# Supplies_LDOs.net
KiCad netlist of a schematic drawn in Altium Designer
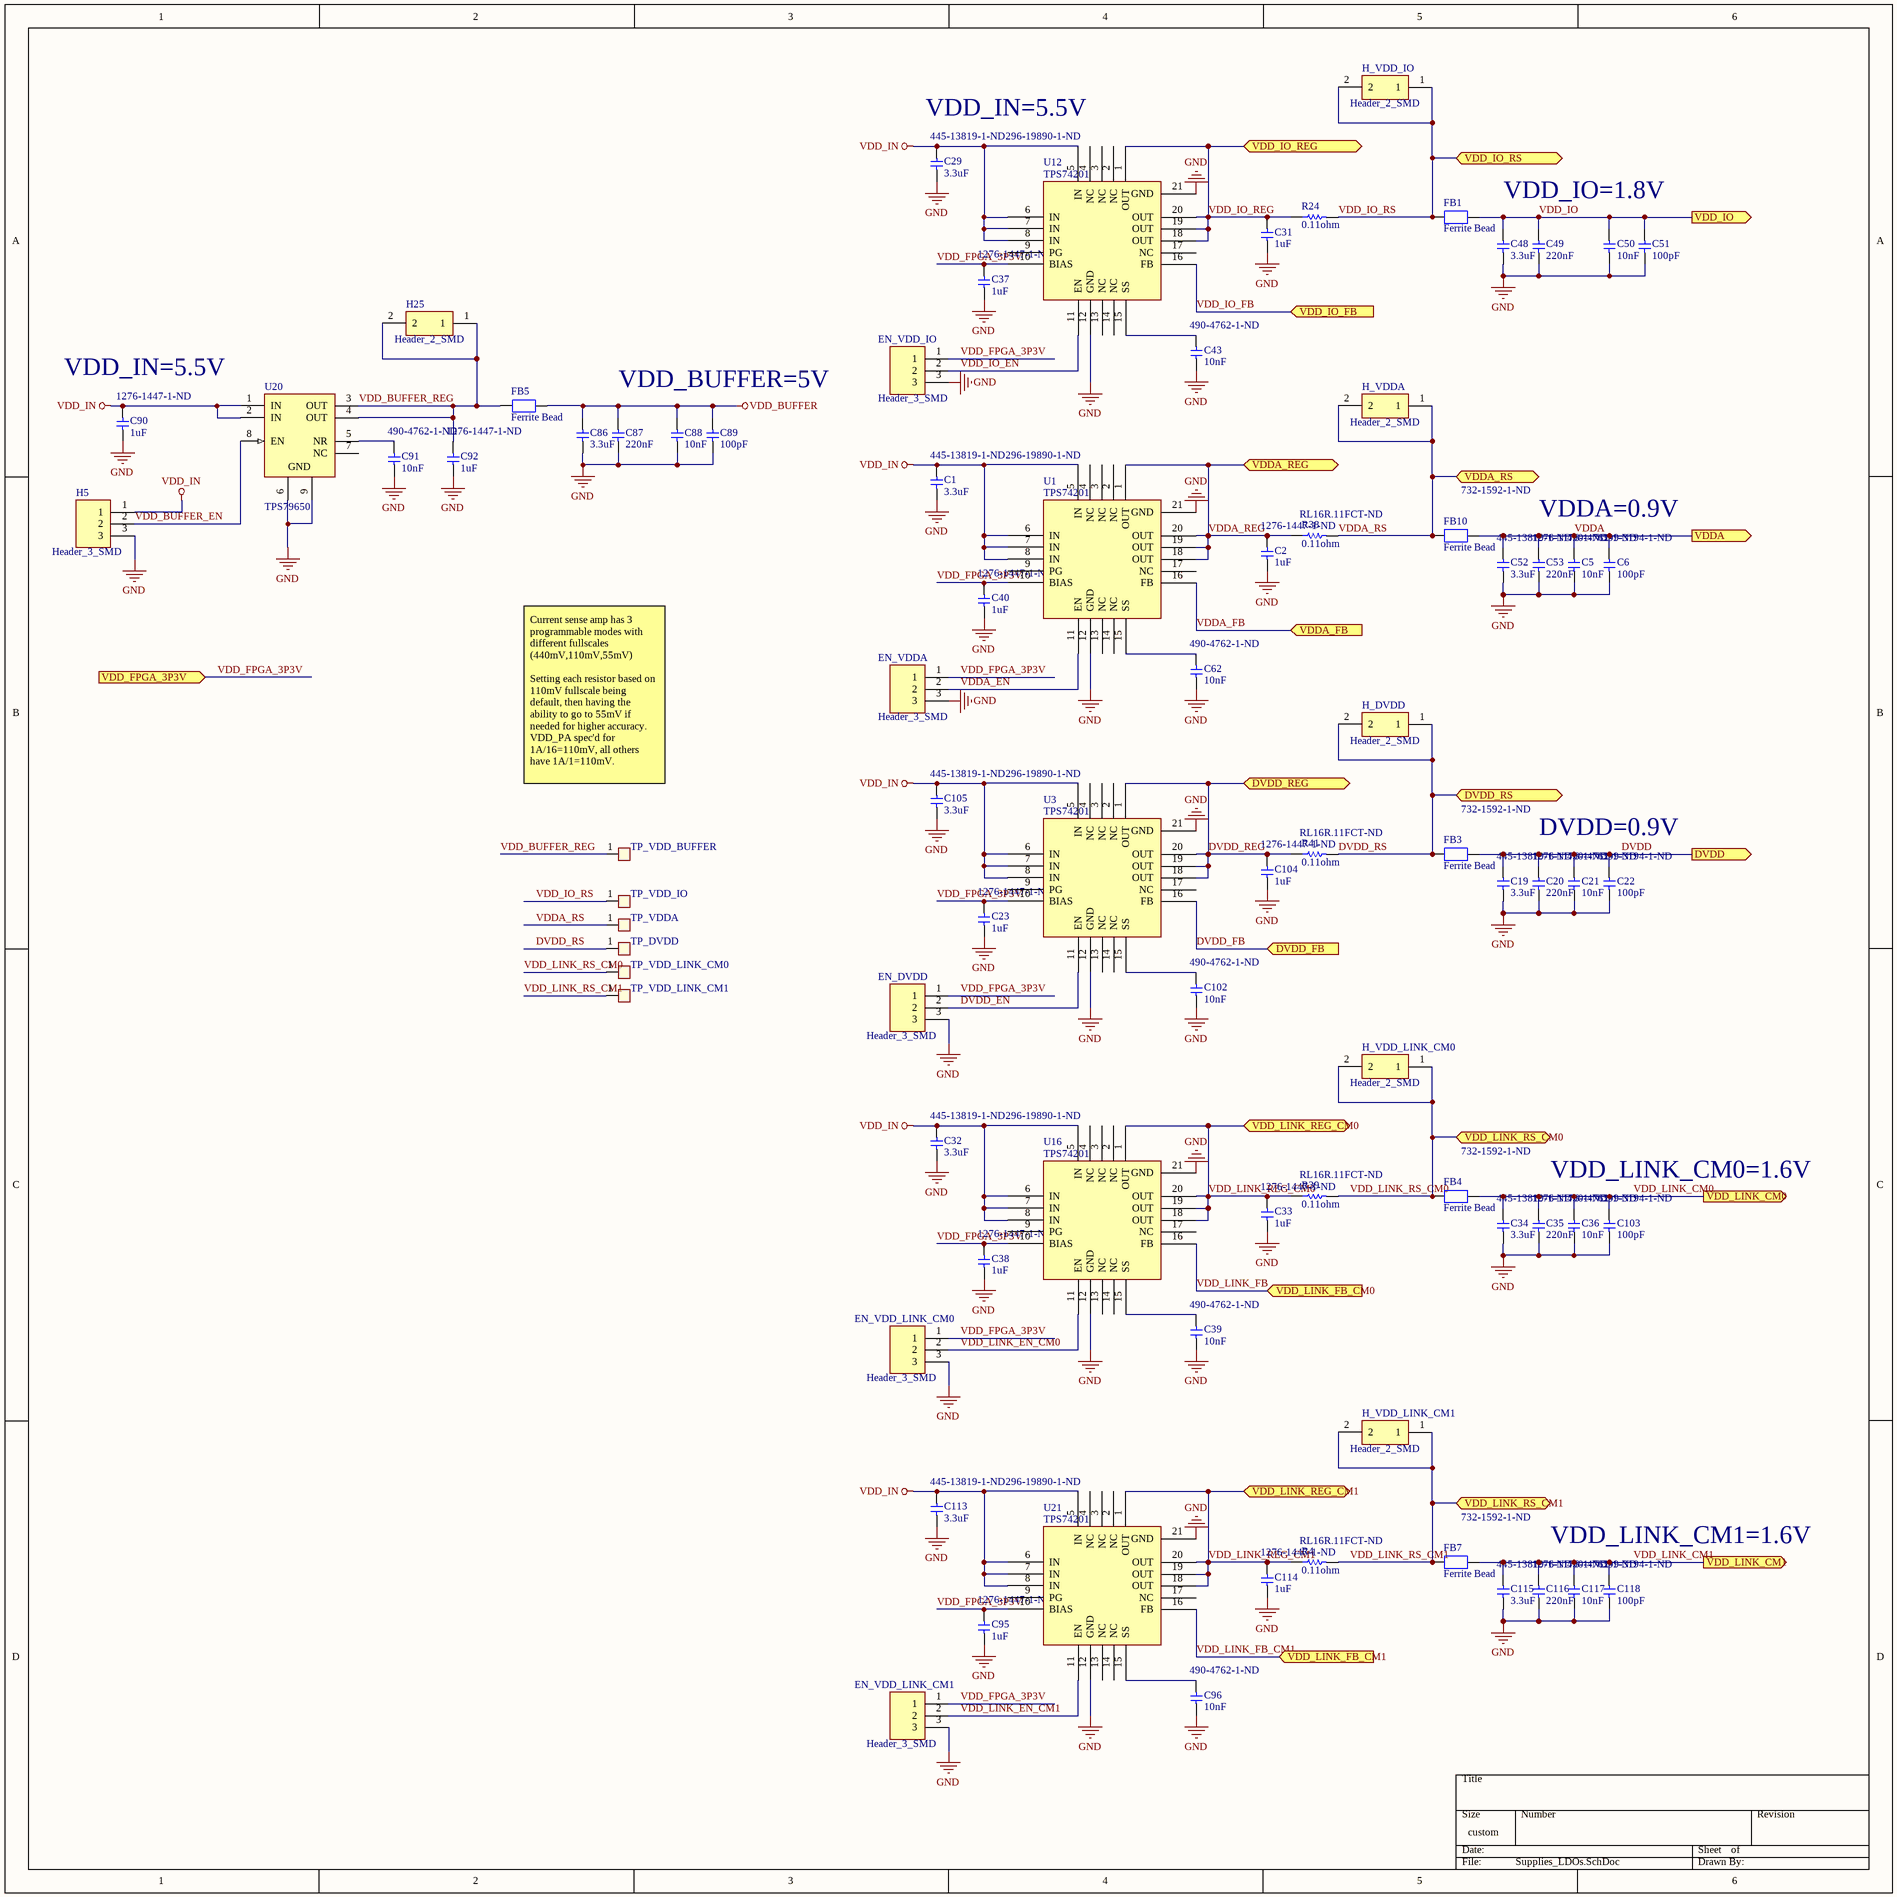
[diagram p0: Supplies_LDOs.SchDoc]

(export (version "E")
  (design (tool "Eeschema 10.0.6"))
  (components
    (comp (ref "C1")
      (value "3.3uF")
      (footprint "CAP_0402")
      (description "CAP CER 3.3uF 10% 10V X5R 0402")
      (fields (field (name "MANUFACTURER") "TDK") (field (name "SUPPLIER PART NUMBER 1") "445-13819-1-ND"))
      (libsource (lib "fader2_parts") (part "cap 3p3uF"))
    )
    (comp (ref "C2")
      (value "1uF")
      (footprint "CAP_0402")
      (description "CAP CER 1uF 20% 16V X5R 0402")
      (fields
        (field (name "MANUFACTURER") "Samsung Electro-Mechanics")
        (field (name "SUPPLIER PART NUMBER 1") "1276-1447-1-ND")
      )
      (libsource (lib "fader2_parts") (part "cap 1uF 0402"))
    )
    (comp (ref "C5")
      (value "10nF")
      (footprint "CAPC1005X06L_HD")
      (description "CAP CER 10nF 10% 50V X7R 0402")
      (fields (field (name "MANUFACTURER") "Murata") (field (name "SUPPLIER PART NUMBER 1") "490-4762-1-ND"))
      (libsource (lib "fader2_parts") (part "cap 10nF"))
    )
    (comp (ref "C6")
      (value "100pF")
      (footprint "CAPC1005X06L_HD")
      (description "CAP CER 100pF 5% 50V C0G/NP0 0402")
      (fields (field (name "MANUFACTURER") "Kemet") (field (name "SUPPLIER PART NUMBER 1") "399-3194-1-ND"))
      (libsource (lib "fader2_parts") (part "cap 100pF 0402"))
    )
    (comp (ref "C19")
      (value "3.3uF")
      (footprint "CAP_0402")
      (description "CAP CER 3.3uF 10% 10V X5R 0402")
      (fields (field (name "MANUFACTURER") "TDK") (field (name "SUPPLIER PART NUMBER 1") "445-13819-1-ND"))
      (libsource (lib "fader2_parts") (part "cap 3p3uF"))
    )
    (comp (ref "C20")
      (value "220nF")
      (footprint "CAP_0402")
      (description "CAP CER 0.22uF 10% 16V X7R 0402")
      (fields
        (field (name "MANUFACTURER") "Samsung Electro-Mechanics")
        (field (name "SUPPLIER PART NUMBER 1") "1276-1176-1-ND")
      )
      (libsource (lib "fader2_parts") (part "cap 220nF"))
    )
    (comp (ref "C21")
      (value "10nF")
      (footprint "CAPC1005X06L_HD")
      (description "CAP CER 10nF 10% 50V X7R 0402")
      (fields (field (name "MANUFACTURER") "Murata") (field (name "SUPPLIER PART NUMBER 1") "490-4762-1-ND"))
      (libsource (lib "fader2_parts") (part "cap 10nF"))
    )
    (comp (ref "C22")
      (value "100pF")
      (footprint "CAPC1005X06L_HD")
      (description "CAP CER 100pF 5% 50V C0G/NP0 0402")
      (fields (field (name "MANUFACTURER") "Kemet") (field (name "SUPPLIER PART NUMBER 1") "399-3194-1-ND"))
      (libsource (lib "fader2_parts") (part "cap 100pF 0402"))
    )
    (comp (ref "C23")
      (value "1uF")
      (footprint "CAP_0402")
      (description "CAP CER 1uF 20% 16V X5R 0402")
      (fields
        (field (name "MANUFACTURER") "Samsung Electro-Mechanics")
        (field (name "SUPPLIER PART NUMBER 1") "1276-1447-1-ND")
      )
      (libsource (lib "fader2_parts") (part "cap 1uF 0402"))
    )
    (comp (ref "C29")
      (value "3.3uF")
      (footprint "CAP_0402")
      (description "CAP CER 3.3uF 10% 10V X5R 0402")
      (fields (field (name "MANUFACTURER") "TDK") (field (name "SUPPLIER PART NUMBER 1") "445-13819-1-ND"))
      (libsource (lib "fader2_parts") (part "cap 3p3uF"))
    )
    (comp (ref "C31")
      (value "1uF")
      (footprint "CAP_0402")
      (description "CAP CER 1uF 20% 16V X5R 0402")
      (fields (field (name "MANUFACTURER") "Samsung Electro-Mechanics"))
      (libsource (lib "fader2_parts") (part "cap 1uF 0402"))
    )
    (comp (ref "C32")
      (value "3.3uF")
      (footprint "CAP_0402")
      (description "CAP CER 3.3uF 10% 10V X5R 0402")
      (fields (field (name "MANUFACTURER") "TDK") (field (name "SUPPLIER PART NUMBER 1") "445-13819-1-ND"))
      (libsource (lib "fader2_parts") (part "cap 3p3uF"))
    )
    (comp (ref "C33")
      (value "1uF")
      (footprint "CAP_0402")
      (description "CAP CER 1uF 20% 16V X5R 0402")
      (fields
        (field (name "MANUFACTURER") "Samsung Electro-Mechanics")
        (field (name "SUPPLIER PART NUMBER 1") "1276-1447-1-ND")
      )
      (libsource (lib "fader2_parts") (part "cap 1uF 0402"))
    )
    (comp (ref "C34")
      (value "3.3uF")
      (footprint "CAP_0402")
      (description "CAP CER 3.3uF 10% 10V X5R 0402")
      (fields (field (name "MANUFACTURER") "TDK") (field (name "SUPPLIER PART NUMBER 1") "445-13819-1-ND"))
      (libsource (lib "fader2_parts") (part "cap 3p3uF"))
    )
    (comp (ref "C35")
      (value "220nF")
      (footprint "CAP_0402")
      (description "CAP CER 0.22uF 10% 16V X7R 0402")
      (fields
        (field (name "MANUFACTURER") "Samsung Electro-Mechanics")
        (field (name "SUPPLIER PART NUMBER 1") "1276-1176-1-ND")
      )
      (libsource (lib "fader2_parts") (part "cap 220nF"))
    )
    (comp (ref "C36")
      (value "10nF")
      (footprint "CAPC1005X06L_HD")
      (description "CAP CER 10nF 10% 50V X7R 0402")
      (fields (field (name "MANUFACTURER") "Murata") (field (name "SUPPLIER PART NUMBER 1") "490-4762-1-ND"))
      (libsource (lib "fader2_parts") (part "cap 10nF"))
    )
    (comp (ref "C37")
      (value "1uF")
      (footprint "CAP_0402")
      (description "CAP CER 1uF 20% 16V X5R 0402")
      (fields
        (field (name "MANUFACTURER") "Samsung Electro-Mechanics")
        (field (name "SUPPLIER PART NUMBER 1") "1276-1447-1-ND")
      )
      (libsource (lib "fader2_parts") (part "cap 1uF 0402"))
    )
    (comp (ref "C38")
      (value "1uF")
      (footprint "CAP_0402")
      (description "CAP CER 1uF 20% 16V X5R 0402")
      (fields
        (field (name "MANUFACTURER") "Samsung Electro-Mechanics")
        (field (name "SUPPLIER PART NUMBER 1") "1276-1447-1-ND")
      )
      (libsource (lib "fader2_parts") (part "cap 1uF 0402"))
    )
    (comp (ref "C39")
      (value "10nF")
      (footprint "CAPC1005X06L_HD")
      (description "CAP CER 10nF 10% 50V X7R 0402")
      (fields (field (name "MANUFACTURER") "Murata") (field (name "SUPPLIER PART NUMBER 1") "490-4762-1-ND"))
      (libsource (lib "fader2_parts") (part "cap 10nF"))
    )
    (comp (ref "C40")
      (value "1uF")
      (footprint "CAP_0402")
      (description "CAP CER 1uF 20% 16V X5R 0402")
      (fields
        (field (name "MANUFACTURER") "Samsung Electro-Mechanics")
        (field (name "SUPPLIER PART NUMBER 1") "1276-1447-1-ND")
      )
      (libsource (lib "fader2_parts") (part "cap 1uF 0402"))
    )
    (comp (ref "C43")
      (value "10nF")
      (footprint "CAPC1005X06L_HD")
      (description "CAP CER 10nF 10% 50V X7R 0402")
      (fields (field (name "MANUFACTURER") "Murata") (field (name "SUPPLIER PART NUMBER 1") "490-4762-1-ND"))
      (libsource (lib "fader2_parts") (part "cap 10nF"))
    )
    (comp (ref "C48")
      (value "3.3uF")
      (footprint "CAP_0402")
      (description "CAP CER 3.3uF 10% 10V X5R 0402")
      (fields (field (name "MANUFACTURER") "TDK"))
      (libsource (lib "fader2_parts") (part "cap 3p3uF"))
    )
    (comp (ref "C49")
      (value "220nF")
      (footprint "CAP_0402")
      (description "CAP CER 0.22uF 10% 16V X7R 0402")
      (fields (field (name "MANUFACTURER") "Samsung Electro-Mechanics"))
      (libsource (lib "fader2_parts") (part "cap 220nF"))
    )
    (comp (ref "C50")
      (value "10nF")
      (footprint "CAPC1005X06L_HD")
      (description "CAP CER 10nF 10% 50V X7R 0402")
      (fields (field (name "MANUFACTURER") "Murata"))
      (libsource (lib "fader2_parts") (part "cap 10nF"))
    )
    (comp (ref "C51")
      (value "100pF")
      (footprint "CAPC1005X06L_HD")
      (description "CAP CER 100pF 5% 50V C0G/NP0 0402")
      (fields (field (name "MANUFACTURER") "Kemet"))
      (libsource (lib "fader2_parts") (part "cap 100pF 0402"))
    )
    (comp (ref "C52")
      (value "3.3uF")
      (footprint "CAP_0402")
      (description "CAP CER 3.3uF 10% 10V X5R 0402")
      (fields (field (name "MANUFACTURER") "TDK") (field (name "SUPPLIER PART NUMBER 1") "445-13819-1-ND"))
      (libsource (lib "fader2_parts") (part "cap 3p3uF"))
    )
    (comp (ref "C53")
      (value "220nF")
      (footprint "CAP_0402")
      (description "CAP CER 0.22uF 10% 16V X7R 0402")
      (fields
        (field (name "MANUFACTURER") "Samsung Electro-Mechanics")
        (field (name "SUPPLIER PART NUMBER 1") "1276-1176-1-ND")
      )
      (libsource (lib "fader2_parts") (part "cap 220nF"))
    )
    (comp (ref "C62")
      (value "10nF")
      (footprint "CAPC1005X06L_HD")
      (description "CAP CER 10nF 10% 50V X7R 0402")
      (fields (field (name "MANUFACTURER") "Murata") (field (name "SUPPLIER PART NUMBER 1") "490-4762-1-ND"))
      (libsource (lib "fader2_parts") (part "cap 10nF"))
    )
    (comp (ref "C86")
      (value "3.3uF")
      (footprint "CAP_0402")
      (description "CAP CER 3.3uF 10% 10V X5R 0402")
      (fields (field (name "MANUFACTURER") "TDK"))
      (libsource (lib "fader2_parts") (part "cap 3p3uF"))
    )
    (comp (ref "C87")
      (value "220nF")
      (footprint "CAP_0402")
      (description "CAP CER 0.22uF 10% 16V X7R 0402")
      (fields (field (name "MANUFACTURER") "Samsung Electro-Mechanics"))
      (libsource (lib "fader2_parts") (part "cap 220nF"))
    )
    (comp (ref "C88")
      (value "10nF")
      (footprint "CAPC1005X06L_HD")
      (description "CAP CER 10nF 10% 50V X7R 0402")
      (fields (field (name "MANUFACTURER") "Murata"))
      (libsource (lib "fader2_parts") (part "cap 10nF"))
    )
    (comp (ref "C89")
      (value "100pF")
      (footprint "CAPC1005X06L_HD")
      (description "CAP CER 100pF 5% 50V C0G/NP0 0402")
      (fields (field (name "MANUFACTURER") "Kemet"))
      (libsource (lib "fader2_parts") (part "cap 100pF 0402"))
    )
    (comp (ref "C90")
      (value "1uF")
      (footprint "CAP_0402")
      (description "CAP CER 1uF 20% 16V X5R 0402")
      (fields
        (field (name "MANUFACTURER") "Samsung Electro-Mechanics")
        (field (name "SUPPLIER PART NUMBER 1") "1276-1447-1-ND")
      )
      (libsource (lib "fader2_parts") (part "cap 1uF 0402"))
    )
    (comp (ref "C91")
      (value "10nF")
      (footprint "CAPC1005X06L_HD")
      (description "CAP CER 10nF 10% 50V X7R 0402")
      (fields (field (name "MANUFACTURER") "Murata") (field (name "SUPPLIER PART NUMBER 1") "490-4762-1-ND"))
      (libsource (lib "fader2_parts") (part "cap 10nF"))
    )
    (comp (ref "C92")
      (value "1uF")
      (footprint "CAP_0402")
      (description "CAP CER 1uF 20% 16V X5R 0402")
      (fields
        (field (name "MANUFACTURER") "Samsung Electro-Mechanics")
        (field (name "SUPPLIER PART NUMBER 1") "1276-1447-1-ND")
      )
      (libsource (lib "fader2_parts") (part "cap 1uF 0402"))
    )
    (comp (ref "C95")
      (value "1uF")
      (footprint "CAP_0402")
      (description "CAP CER 1uF 20% 16V X5R 0402")
      (fields
        (field (name "MANUFACTURER") "Samsung Electro-Mechanics")
        (field (name "SUPPLIER PART NUMBER 1") "1276-1447-1-ND")
      )
      (libsource (lib "fader2_parts") (part "cap 1uF 0402"))
    )
    (comp (ref "C96")
      (value "10nF")
      (footprint "CAPC1005X06L_HD")
      (description "CAP CER 10nF 10% 50V X7R 0402")
      (fields (field (name "MANUFACTURER") "Murata") (field (name "SUPPLIER PART NUMBER 1") "490-4762-1-ND"))
      (libsource (lib "fader2_parts") (part "cap 10nF"))
    )
    (comp (ref "C102")
      (value "10nF")
      (footprint "CAPC1005X06L_HD")
      (description "CAP CER 10nF 10% 50V X7R 0402")
      (fields (field (name "MANUFACTURER") "Murata") (field (name "SUPPLIER PART NUMBER 1") "490-4762-1-ND"))
      (libsource (lib "fader2_parts") (part "cap 10nF"))
    )
    (comp (ref "C103")
      (value "100pF")
      (footprint "CAPC1005X06L_HD")
      (description "CAP CER 100pF 5% 50V C0G/NP0 0402")
      (fields (field (name "MANUFACTURER") "Kemet") (field (name "SUPPLIER PART NUMBER 1") "399-3194-1-ND"))
      (libsource (lib "fader2_parts") (part "cap 100pF 0402"))
    )
    (comp (ref "C104")
      (value "1uF")
      (footprint "CAP_0402")
      (description "CAP CER 1uF 20% 16V X5R 0402")
      (fields
        (field (name "MANUFACTURER") "Samsung Electro-Mechanics")
        (field (name "SUPPLIER PART NUMBER 1") "1276-1447-1-ND")
      )
      (libsource (lib "fader2_parts") (part "cap 1uF 0402"))
    )
    (comp (ref "C105")
      (value "3.3uF")
      (footprint "CAP_0402")
      (description "CAP CER 3.3uF 10% 10V X5R 0402")
      (fields (field (name "MANUFACTURER") "TDK") (field (name "SUPPLIER PART NUMBER 1") "445-13819-1-ND"))
      (libsource (lib "fader2_parts") (part "cap 3p3uF"))
    )
    (comp (ref "C113")
      (value "3.3uF")
      (footprint "CAP_0402")
      (description "CAP CER 3.3uF 10% 10V X5R 0402")
      (fields (field (name "MANUFACTURER") "TDK") (field (name "SUPPLIER PART NUMBER 1") "445-13819-1-ND"))
      (libsource (lib "fader2_parts") (part "cap 3p3uF"))
    )
    (comp (ref "C114")
      (value "1uF")
      (footprint "CAP_0402")
      (description "CAP CER 1uF 20% 16V X5R 0402")
      (fields
        (field (name "MANUFACTURER") "Samsung Electro-Mechanics")
        (field (name "SUPPLIER PART NUMBER 1") "1276-1447-1-ND")
      )
      (libsource (lib "fader2_parts") (part "cap 1uF 0402"))
    )
    (comp (ref "C115")
      (value "3.3uF")
      (footprint "CAP_0402")
      (description "CAP CER 3.3uF 10% 10V X5R 0402")
      (fields (field (name "MANUFACTURER") "TDK") (field (name "SUPPLIER PART NUMBER 1") "445-13819-1-ND"))
      (libsource (lib "fader2_parts") (part "cap 3p3uF"))
    )
    (comp (ref "C116")
      (value "220nF")
      (footprint "CAP_0402")
      (description "CAP CER 0.22uF 10% 16V X7R 0402")
      (fields
        (field (name "MANUFACTURER") "Samsung Electro-Mechanics")
        (field (name "SUPPLIER PART NUMBER 1") "1276-1176-1-ND")
      )
      (libsource (lib "fader2_parts") (part "cap 220nF"))
    )
    (comp (ref "C117")
      (value "10nF")
      (footprint "CAPC1005X06L_HD")
      (description "CAP CER 10nF 10% 50V X7R 0402")
      (fields (field (name "MANUFACTURER") "Murata") (field (name "SUPPLIER PART NUMBER 1") "490-4762-1-ND"))
      (libsource (lib "fader2_parts") (part "cap 10nF"))
    )
    (comp (ref "C118")
      (value "100pF")
      (footprint "CAPC1005X06L_HD")
      (description "CAP CER 100pF 5% 50V C0G/NP0 0402")
      (fields (field (name "MANUFACTURER") "Kemet") (field (name "SUPPLIER PART NUMBER 1") "399-3194-1-ND"))
      (libsource (lib "fader2_parts") (part "cap 100pF 0402"))
    )
    (comp (ref "EN_DVDD")
      (value "Header_3_SMD")
      (footprint "HDR1X3_SMD")
      (description "Connector Header Vertical, SMD, 3 position 0.100\" (2.54mm)")
      (fields
        (field (name "MANUFACTURER_PART_NUMBER") "TSM-103-01-S-SV-P-TR")
        (field (name "MOUSER PART NUMBER") "200-TSM10301SSVPTR")
      )
      (libsource (lib "fader2_parts") (part "Header_3_SMD"))
    )
    (comp (ref "EN_VDDA")
      (value "Header_3_SMD")
      (footprint "HDR1X3_SMD")
      (description "Connector Header Vertical, SMD, 3 position 0.100\" (2.54mm)")
      (fields
        (field (name "MANUFACTURER_PART_NUMBER") "TSM-103-01-S-SV-P-TR")
        (field (name "MOUSER PART NUMBER") "200-TSM10301SSVPTR")
      )
      (libsource (lib "fader2_parts") (part "Header_3_SMD"))
    )
    (comp (ref "EN_VDD_IO")
      (value "Header_3_SMD")
      (footprint "HDR1X3_SMD")
      (description "Connector Header Vertical, SMD, 3 position 0.100\" (2.54mm)")
      (fields
        (field (name "MANUFACTURER_PART_NUMBER") "TSM-103-01-S-SV-P-TR")
        (field (name "MOUSER PART NUMBER") "200-TSM10301SSVPTR")
      )
      (libsource (lib "fader2_parts") (part "Header_3_SMD"))
    )
    (comp (ref "EN_VDD_LINK_CM0")
      (value "Header_3_SMD")
      (footprint "HDR1X3_SMD")
      (description "Connector Header Vertical, SMD, 3 position 0.100\" (2.54mm)")
      (fields
        (field (name "MANUFACTURER_PART_NUMBER") "TSM-103-01-S-SV-P-TR")
        (field (name "MOUSER PART NUMBER") "200-TSM10301SSVPTR")
      )
      (libsource (lib "fader2_parts") (part "Header_3_SMD"))
    )
    (comp (ref "EN_VDD_LINK_CM1")
      (value "Header_3_SMD")
      (footprint "HDR1X3_SMD")
      (description "Connector Header Vertical, SMD, 3 position 0.100\" (2.54mm)")
      (fields
        (field (name "MANUFACTURER_PART_NUMBER") "TSM-103-01-S-SV-P-TR")
        (field (name "MOUSER PART NUMBER") "200-TSM10301SSVPTR")
      )
      (libsource (lib "fader2_parts") (part "Header_3_SMD"))
    )
    (comp (ref "FB1")
      (value "Ferrite Bead")
      (footprint "FER_SMD-0603")
      (description "Ferrite Bead 300 Ohms @ 100MHz 1 Signal Line 0603 (1608 Metric) 2A 150mOhm")
      (fields (field (name "MANUFACTURER") "Wurth"))
      (libsource (lib "fader2_parts") (part "Ferrite Bead"))
    )
    (comp (ref "FB3")
      (value "Ferrite Bead")
      (footprint "FER_SMD-0603")
      (description "Ferrite Bead 300 Ohms @ 100MHz 1 Signal Line 0603 (1608 Metric) 2A 150mOhm")
      (fields (field (name "MANUFACTURER") "Wurth") (field (name "SUPPLIER PART NUMBER 1") "732-1592-1-ND"))
      (libsource (lib "fader2_parts") (part "Ferrite Bead"))
    )
    (comp (ref "FB4")
      (value "Ferrite Bead")
      (footprint "FER_SMD-0603")
      (description "Ferrite Bead 300 Ohms @ 100MHz 1 Signal Line 0603 (1608 Metric) 2A 150mOhm")
      (fields (field (name "MANUFACTURER") "Wurth") (field (name "SUPPLIER PART NUMBER 1") "732-1592-1-ND"))
      (libsource (lib "fader2_parts") (part "Ferrite Bead"))
    )
    (comp (ref "FB5")
      (value "Ferrite Bead")
      (footprint "FER_SMD-0603")
      (description "Ferrite Bead 300 Ohms @ 100MHz 1 Signal Line 0603 (1608 Metric) 2A 150mOhm")
      (fields (field (name "MANUFACTURER") "Wurth"))
      (libsource (lib "fader2_parts") (part "Ferrite Bead"))
    )
    (comp (ref "FB7")
      (value "Ferrite Bead")
      (footprint "FER_SMD-0603")
      (description "Ferrite Bead 300 Ohms @ 100MHz 1 Signal Line 0603 (1608 Metric) 2A 150mOhm")
      (fields (field (name "MANUFACTURER") "Wurth") (field (name "SUPPLIER PART NUMBER 1") "732-1592-1-ND"))
      (libsource (lib "fader2_parts") (part "Ferrite Bead"))
    )
    (comp (ref "FB10")
      (value "Ferrite Bead")
      (footprint "FER_SMD-0603")
      (description "Ferrite Bead 300 Ohms @ 100MHz 1 Signal Line 0603 (1608 Metric) 2A 150mOhm")
      (fields (field (name "MANUFACTURER") "Wurth") (field (name "SUPPLIER PART NUMBER 1") "732-1592-1-ND"))
      (libsource (lib "fader2_parts") (part "Ferrite Bead"))
    )
    (comp (ref "H5")
      (value "Header_3_SMD")
      (footprint "HDR1X3_SMD")
      (description "Connector Header Vertical, SMD, 3 position 0.100\" (2.54mm)")
      (fields
        (field (name "MANUFACTURER_PART_NUMBER") "TSM-103-01-S-SV-P-TR")
        (field (name "MOUSER PART NUMBER") "200-TSM10301SSVPTR")
      )
      (libsource (lib "fader2_parts") (part "Header_3_SMD"))
    )
    (comp (ref "H25")
      (value "Header_2_SMD")
      (footprint "HDR1X2_SMD_S")
      (description "Connector Header Vertical, SMD, 2 position 0.100\" (2.54mm)")
      (fields
        (field (name "MANUFACTURER_PART_NUMBER") "TSM-102-01-S-SV")
        (field (name "MOUSER PART NUMBER") "200-TSM10201SSV")
      )
      (libsource (lib "fader2_parts") (part "Header_2_SMD"))
    )
    (comp (ref "H_DVDD")
      (value "Header_2_SMD")
      (footprint "HDR1X2_SMD_S")
      (description "Connector Header Vertical, SMD, 2 position 0.100\" (2.54mm)")
      (fields
        (field (name "MANUFACTURER_PART_NUMBER") "TSM-102-01-S-SV")
        (field (name "MOUSER PART NUMBER") "200-TSM10201SSV")
      )
      (libsource (lib "fader2_parts") (part "Header_2_SMD"))
    )
    (comp (ref "H_VDDA")
      (value "Header_2_SMD")
      (footprint "HDR1X2_SMD_S")
      (description "Connector Header Vertical, SMD, 2 position 0.100\" (2.54mm)")
      (fields
        (field (name "MANUFACTURER_PART_NUMBER") "TSM-102-01-S-SV")
        (field (name "MOUSER PART NUMBER") "200-TSM10201SSV")
      )
      (libsource (lib "fader2_parts") (part "Header_2_SMD"))
    )
    (comp (ref "H_VDD_IO")
      (value "Header_2_SMD")
      (footprint "HDR1X2_SMD_S")
      (description "Connector Header Vertical, SMD, 2 position 0.100\" (2.54mm)")
      (fields
        (field (name "MANUFACTURER_PART_NUMBER") "TSM-102-01-S-SV")
        (field (name "MOUSER PART NUMBER") "200-TSM10201SSV")
      )
      (libsource (lib "fader2_parts") (part "Header_2_SMD"))
    )
    (comp (ref "H_VDD_LINK_CM0")
      (value "Header_2_SMD")
      (footprint "HDR1X2_SMD_S")
      (description "Connector Header Vertical, SMD, 2 position 0.100\" (2.54mm)")
      (fields
        (field (name "MANUFACTURER_PART_NUMBER") "TSM-102-01-S-SV")
        (field (name "MOUSER PART NUMBER") "200-TSM10201SSV")
      )
      (libsource (lib "fader2_parts") (part "Header_2_SMD"))
    )
    (comp (ref "H_VDD_LINK_CM1")
      (value "Header_2_SMD")
      (footprint "HDR1X2_SMD_S")
      (description "Connector Header Vertical, SMD, 2 position 0.100\" (2.54mm)")
      (fields
        (field (name "MANUFACTURER_PART_NUMBER") "TSM-102-01-S-SV")
        (field (name "MOUSER PART NUMBER") "200-TSM10201SSV")
      )
      (libsource (lib "fader2_parts") (part "Header_2_SMD"))
    )
    (comp (ref "R4")
      (value "0.11ohm")
      (footprint "RES_1206")
      (description "RES 0.11 OHM 1% 1/2W 1206")
      (fields (field (name "MANUFACTURER") "Susumu") (field (name "SUPPLIER PART NUMBER 1") "RL16R.11FCT-ND"))
      (libsource (lib "fader2_parts") (part "res 0.11 ohm"))
    )
    (comp (ref "R24")
      (value "0.11ohm")
      (footprint "RES_1206")
      (description "RES 0.11 OHM 1% 1/2W 1206")
      (fields (field (name "MANUFACTURER") "Susumu"))
      (libsource (lib "fader2_parts") (part "res 0.11 ohm"))
    )
    (comp (ref "R38")
      (value "0.11ohm")
      (footprint "RES_1206")
      (description "RES 0.11 OHM 1% 1/2W 1206")
      (fields (field (name "MANUFACTURER") "Susumu") (field (name "SUPPLIER PART NUMBER 1") "RL16R.11FCT-ND"))
      (libsource (lib "fader2_parts") (part "res 0.11 ohm"))
    )
    (comp (ref "R39")
      (value "0.11ohm")
      (footprint "RES_1206")
      (description "RES 0.11 OHM 1% 1/2W 1206")
      (fields (field (name "MANUFACTURER") "Susumu") (field (name "SUPPLIER PART NUMBER 1") "RL16R.11FCT-ND"))
      (libsource (lib "fader2_parts") (part "res 0.11 ohm"))
    )
    (comp (ref "R41")
      (value "0.11ohm")
      (footprint "RES_1206")
      (description "RES 0.11 OHM 1% 1/2W 1206")
      (fields (field (name "MANUFACTURER") "Susumu") (field (name "SUPPLIER PART NUMBER 1") "RL16R.11FCT-ND"))
      (libsource (lib "fader2_parts") (part "res 0.11 ohm"))
    )
    (comp (ref "TP_DVDD")
      (value "TestPoint_SMD")
      (footprint "TestPoint_SMD")
      (description "Test Point, SMD 1mm x 1.8mm, 1.15mm high.")
      (libsource (lib "fader2_parts") (part "TestPoint_SMD"))
    )
    (comp (ref "TP_VDDA")
      (value "TestPoint_SMD")
      (footprint "TestPoint_SMD")
      (description "Test Point, SMD 1mm x 1.8mm, 1.15mm high.")
      (libsource (lib "fader2_parts") (part "TestPoint_SMD"))
    )
    (comp (ref "TP_VDD_BUFFER")
      (value "TestPoint_SMD")
      (footprint "TestPoint_SMD")
      (description "Test Point, SMD 1mm x 1.8mm, 1.15mm high.")
      (libsource (lib "fader2_parts") (part "TestPoint_SMD"))
    )
    (comp (ref "TP_VDD_IO")
      (value "TestPoint_SMD")
      (footprint "TestPoint_SMD")
      (description "Test Point, SMD 1mm x 1.8mm, 1.15mm high.")
      (libsource (lib "fader2_parts") (part "TestPoint_SMD"))
    )
    (comp (ref "TP_VDD_LINK_CM0")
      (value "TestPoint_SMD")
      (footprint "TestPoint_SMD")
      (description "Test Point, SMD 1mm x 1.8mm, 1.15mm high.")
      (libsource (lib "fader2_parts") (part "TestPoint_SMD"))
    )
    (comp (ref "TP_VDD_LINK_CM1")
      (value "TestPoint_SMD")
      (footprint "TestPoint_SMD")
      (description "Test Point, SMD 1mm x 1.8mm, 1.15mm high.")
      (libsource (lib "fader2_parts") (part "TestPoint_SMD"))
    )
    (comp (ref "U1")
      (value "TPS74201")
      (footprint "TPS74201_NPV")
      (description "Linear Positive Voltage Regulator IC, Adjustable Voltage, 1 Output 1.5A 20-VQFN (5x5)")
      (fields (field (name "MANUFACTURER") "TI") (field (name "SUPPLIER PART NUMBER 1") "296-19890-1-ND"))
      (libsource (lib "fader2_parts") (part "TPS74201"))
    )
    (comp (ref "U3")
      (value "TPS74201")
      (footprint "TPS74201_NPV")
      (description "Linear Positive Voltage Regulator IC, Adjustable Voltage, 1 Output 1.5A 20-VQFN (5x5)")
      (fields (field (name "MANUFACTURER") "TI") (field (name "SUPPLIER PART NUMBER 1") "296-19890-1-ND"))
      (libsource (lib "fader2_parts") (part "TPS74201"))
    )
    (comp (ref "U12")
      (value "TPS74201")
      (footprint "TPS74201_NPV")
      (description "Linear Positive Voltage Regulator IC, Adjustable Voltage, 1 Output 1.5A 20-VQFN (5x5)")
      (fields (field (name "MANUFACTURER") "TI") (field (name "SUPPLIER PART NUMBER 1") "296-19890-1-ND"))
      (libsource (lib "fader2_parts") (part "TPS74201"))
    )
    (comp (ref "U16")
      (value "TPS74201")
      (footprint "TPS74201_NPV")
      (description "Linear Positive Voltage Regulator IC, Adjustable Voltage, 1 Output 1.5A 20-VQFN (5x5)")
      (fields (field (name "MANUFACTURER") "TI") (field (name "SUPPLIER PART NUMBER 1") "296-19890-1-ND"))
      (libsource (lib "fader2_parts") (part "TPS74201"))
    )
    (comp (ref "U20")
      (value "TPS79650")
      (footprint "TI-DRB8-2400X1650TP_V")
      (fields (field (name "MANUFACTURER") "Texas Instruments") (field (name "PARTNUMBER") "TPS79650DRBR"))
      (libsource (lib "fader2_parts") (part "TPS79650DRBR"))
    )
    (comp (ref "U21")
      (value "TPS74201")
      (footprint "TPS74201_NPV")
      (description "Linear Positive Voltage Regulator IC, Adjustable Voltage, 1 Output 1.5A 20-VQFN (5x5)")
      (fields (field (name "MANUFACTURER") "TI") (field (name "SUPPLIER PART NUMBER 1") "296-19890-1-ND"))
      (libsource (lib "fader2_parts") (part "TPS74201"))
    )
  )
  (nets
    (net (code "1") (name "/DVDD") (class "Default")
      (node (ref "C19") (pin "1") (pinfunction "1_1") (pintype "passive"))
      (node (ref "C20") (pin "1") (pinfunction "1_1") (pintype "passive"))
      (node (ref "C21") (pin "1") (pinfunction "1_1") (pintype "passive"))
      (node (ref "C22") (pin "1") (pinfunction "1_1") (pintype "passive"))
      (node (ref "FB3") (pin "2") (pinfunction "2_2") (pintype "passive"))
    )
    (net (code "2") (name "/DVDD_EN") (class "Default")
      (node (ref "EN_DVDD") (pin "2") (pinfunction "2_2") (pintype "passive"))
      (node (ref "U3") (pin "11") (pinfunction "EN_11") (pintype "passive"))
    )
    (net (code "3") (name "/DVDD_FB") (class "Default")
      (node (ref "U3") (pin "16") (pinfunction "FB_16") (pintype "passive"))
    )
    (net (code "4") (name "/DVDD_REG") (class "Default")
      (node (ref "C104") (pin "1") (pinfunction "1_1") (pintype "passive"))
      (node (ref "R41") (pin "1") (pinfunction "TOP_1") (pintype "passive"))
      (node (ref "U3") (pin "1") (pinfunction "OUT_1") (pintype "passive"))
      (node (ref "U3") (pin "18") (pinfunction "OUT_18") (pintype "passive"))
      (node (ref "U3") (pin "19") (pinfunction "OUT_19") (pintype "passive"))
      (node (ref "U3") (pin "20") (pinfunction "OUT_20") (pintype "passive"))
    )
    (net (code "5") (name "/DVDD_RS") (class "Default")
      (node (ref "FB3") (pin "1") (pinfunction "1_1") (pintype "passive"))
      (node (ref "H_DVDD") (pin "1") (pinfunction "1_1") (pintype "passive"))
      (node (ref "H_DVDD") (pin "2") (pinfunction "2_2") (pintype "passive"))
      (node (ref "R41") (pin "2") (pinfunction "BOT_2") (pintype "passive"))
      (node (ref "TP_DVDD") (pin "1") (pinfunction "TP_1") (pintype "passive"))
    )
    (net (code "6") (name "/VDDA") (class "Default")
      (node (ref "C5") (pin "1") (pinfunction "1_1") (pintype "passive"))
      (node (ref "C52") (pin "1") (pinfunction "1_1") (pintype "passive"))
      (node (ref "C53") (pin "1") (pinfunction "1_1") (pintype "passive"))
      (node (ref "C6") (pin "1") (pinfunction "1_1") (pintype "passive"))
      (node (ref "FB10") (pin "2") (pinfunction "2_2") (pintype "passive"))
    )
    (net (code "7") (name "/VDDA_EN") (class "Default")
      (node (ref "EN_VDDA") (pin "2") (pinfunction "2_2") (pintype "passive"))
      (node (ref "U1") (pin "11") (pinfunction "EN_11") (pintype "passive"))
    )
    (net (code "8") (name "/VDDA_FB") (class "Default")
      (node (ref "U1") (pin "16") (pinfunction "FB_16") (pintype "passive"))
    )
    (net (code "9") (name "/VDDA_REG") (class "Default")
      (node (ref "C2") (pin "1") (pinfunction "1_1") (pintype "passive"))
      (node (ref "R38") (pin "1") (pinfunction "TOP_1") (pintype "passive"))
      (node (ref "U1") (pin "1") (pinfunction "OUT_1") (pintype "passive"))
      (node (ref "U1") (pin "18") (pinfunction "OUT_18") (pintype "passive"))
      (node (ref "U1") (pin "19") (pinfunction "OUT_19") (pintype "passive"))
      (node (ref "U1") (pin "20") (pinfunction "OUT_20") (pintype "passive"))
    )
    (net (code "10") (name "/VDDA_RS") (class "Default")
      (node (ref "FB10") (pin "1") (pinfunction "1_1") (pintype "passive"))
      (node (ref "H_VDDA") (pin "1") (pinfunction "1_1") (pintype "passive"))
      (node (ref "H_VDDA") (pin "2") (pinfunction "2_2") (pintype "passive"))
      (node (ref "R38") (pin "2") (pinfunction "BOT_2") (pintype "passive"))
      (node (ref "TP_VDDA") (pin "1") (pinfunction "TP_1") (pintype "passive"))
    )
    (net (code "11") (name "/VDD_BUFFER_EN") (class "Default")
      (node (ref "H5") (pin "2") (pinfunction "2_2") (pintype "passive"))
      (node (ref "U20") (pin "8") (pinfunction "EN_8") (pintype "input"))
    )
    (net (code "12") (name "/VDD_BUFFER_REG") (class "Default")
      (node (ref "C92") (pin "1") (pinfunction "1_1") (pintype "passive"))
      (node (ref "FB5") (pin "1") (pinfunction "1_1") (pintype "passive"))
      (node (ref "H25") (pin "1") (pinfunction "1_1") (pintype "passive"))
      (node (ref "H25") (pin "2") (pinfunction "2_2") (pintype "passive"))
      (node (ref "TP_VDD_BUFFER") (pin "1") (pinfunction "TP_1") (pintype "passive"))
      (node (ref "U20") (pin "3") (pinfunction "OUT_3") (pintype "power_in"))
      (node (ref "U20") (pin "4") (pinfunction "OUT_4") (pintype "power_in"))
    )
    (net (code "13") (name "/VDD_FPGA_3P3V") (class "Default")
      (node (ref "C23") (pin "1") (pinfunction "1_1") (pintype "passive"))
      (node (ref "C37") (pin "1") (pinfunction "1_1") (pintype "passive"))
      (node (ref "C38") (pin "1") (pinfunction "1_1") (pintype "passive"))
      (node (ref "C40") (pin "1") (pinfunction "1_1") (pintype "passive"))
      (node (ref "C95") (pin "1") (pinfunction "1_1") (pintype "passive"))
      (node (ref "EN_DVDD") (pin "1") (pinfunction "1_1") (pintype "passive"))
      (node (ref "EN_VDDA") (pin "1") (pinfunction "1_1") (pintype "passive"))
      (node (ref "EN_VDD_IO") (pin "1") (pinfunction "1_1") (pintype "passive"))
      (node (ref "EN_VDD_LINK_CM0") (pin "1") (pinfunction "1_1") (pintype "passive"))
      (node (ref "EN_VDD_LINK_CM1") (pin "1") (pinfunction "1_1") (pintype "passive"))
      (node (ref "U1") (pin "10") (pinfunction "BIAS_10") (pintype "passive"))
      (node (ref "U12") (pin "10") (pinfunction "BIAS_10") (pintype "passive"))
      (node (ref "U16") (pin "10") (pinfunction "BIAS_10") (pintype "passive"))
      (node (ref "U21") (pin "10") (pinfunction "BIAS_10") (pintype "passive"))
      (node (ref "U3") (pin "10") (pinfunction "BIAS_10") (pintype "passive"))
    )
    (net (code "14") (name "/VDD_IO") (class "Default")
      (node (ref "C48") (pin "1") (pinfunction "1_1") (pintype "passive"))
      (node (ref "C49") (pin "1") (pinfunction "1_1") (pintype "passive"))
      (node (ref "C50") (pin "1") (pinfunction "1_1") (pintype "passive"))
      (node (ref "C51") (pin "1") (pinfunction "1_1") (pintype "passive"))
      (node (ref "FB1") (pin "2") (pinfunction "2_2") (pintype "passive"))
    )
    (net (code "15") (name "/VDD_IO_EN") (class "Default")
      (node (ref "EN_VDD_IO") (pin "2") (pinfunction "2_2") (pintype "passive"))
      (node (ref "U12") (pin "11") (pinfunction "EN_11") (pintype "passive"))
    )
    (net (code "16") (name "/VDD_IO_FB") (class "Default")
      (node (ref "U12") (pin "16") (pinfunction "FB_16") (pintype "passive"))
    )
    (net (code "17") (name "/VDD_IO_REG") (class "Default")
      (node (ref "C31") (pin "1") (pinfunction "1_1") (pintype "passive"))
      (node (ref "R24") (pin "1") (pinfunction "TOP_1") (pintype "passive"))
      (node (ref "U12") (pin "1") (pinfunction "OUT_1") (pintype "passive"))
      (node (ref "U12") (pin "18") (pinfunction "OUT_18") (pintype "passive"))
      (node (ref "U12") (pin "19") (pinfunction "OUT_19") (pintype "passive"))
      (node (ref "U12") (pin "20") (pinfunction "OUT_20") (pintype "passive"))
    )
    (net (code "18") (name "/VDD_IO_RS") (class "Default")
      (node (ref "FB1") (pin "1") (pinfunction "1_1") (pintype "passive"))
      (node (ref "H_VDD_IO") (pin "1") (pinfunction "1_1") (pintype "passive"))
      (node (ref "H_VDD_IO") (pin "2") (pinfunction "2_2") (pintype "passive"))
      (node (ref "R24") (pin "2") (pinfunction "BOT_2") (pintype "passive"))
      (node (ref "TP_VDD_IO") (pin "1") (pinfunction "TP_1") (pintype "passive"))
    )
    (net (code "19") (name "/VDD_LINK_CM0") (class "Default")
      (node (ref "C103") (pin "1") (pinfunction "1_1") (pintype "passive"))
      (node (ref "C34") (pin "1") (pinfunction "1_1") (pintype "passive"))
      (node (ref "C35") (pin "1") (pinfunction "1_1") (pintype "passive"))
      (node (ref "C36") (pin "1") (pinfunction "1_1") (pintype "passive"))
      (node (ref "FB4") (pin "2") (pinfunction "2_2") (pintype "passive"))
    )
    (net (code "20") (name "/VDD_LINK_CM1") (class "Default")
      (node (ref "C115") (pin "1") (pinfunction "1_1") (pintype "passive"))
      (node (ref "C116") (pin "1") (pinfunction "1_1") (pintype "passive"))
      (node (ref "C117") (pin "1") (pinfunction "1_1") (pintype "passive"))
      (node (ref "C118") (pin "1") (pinfunction "1_1") (pintype "passive"))
      (node (ref "FB7") (pin "2") (pinfunction "2_2") (pintype "passive"))
    )
    (net (code "21") (name "/VDD_LINK_EN_CM0") (class "Default")
      (node (ref "EN_VDD_LINK_CM0") (pin "2") (pinfunction "2_2") (pintype "passive"))
      (node (ref "U16") (pin "11") (pinfunction "EN_11") (pintype "passive"))
    )
    (net (code "22") (name "/VDD_LINK_EN_CM1") (class "Default")
      (node (ref "EN_VDD_LINK_CM1") (pin "2") (pinfunction "2_2") (pintype "passive"))
      (node (ref "U21") (pin "11") (pinfunction "EN_11") (pintype "passive"))
    )
    (net (code "23") (name "/VDD_LINK_FB") (class "Default")
      (node (ref "U16") (pin "16") (pinfunction "FB_16") (pintype "passive"))
    )
    (net (code "24") (name "/VDD_LINK_FB_CM1") (class "Default")
      (node (ref "U21") (pin "16") (pinfunction "FB_16") (pintype "passive"))
    )
    (net (code "25") (name "/VDD_LINK_REG_CM0") (class "Default")
      (node (ref "C33") (pin "1") (pinfunction "1_1") (pintype "passive"))
      (node (ref "R39") (pin "1") (pinfunction "TOP_1") (pintype "passive"))
      (node (ref "U16") (pin "1") (pinfunction "OUT_1") (pintype "passive"))
      (node (ref "U16") (pin "18") (pinfunction "OUT_18") (pintype "passive"))
      (node (ref "U16") (pin "19") (pinfunction "OUT_19") (pintype "passive"))
      (node (ref "U16") (pin "20") (pinfunction "OUT_20") (pintype "passive"))
    )
    (net (code "26") (name "/VDD_LINK_REG_CM1") (class "Default")
      (node (ref "C114") (pin "1") (pinfunction "1_1") (pintype "passive"))
      (node (ref "R4") (pin "1") (pinfunction "TOP_1") (pintype "passive"))
      (node (ref "U21") (pin "1") (pinfunction "OUT_1") (pintype "passive"))
      (node (ref "U21") (pin "18") (pinfunction "OUT_18") (pintype "passive"))
      (node (ref "U21") (pin "19") (pinfunction "OUT_19") (pintype "passive"))
      (node (ref "U21") (pin "20") (pinfunction "OUT_20") (pintype "passive"))
    )
    (net (code "27") (name "/VDD_LINK_RS_CM0") (class "Default")
      (node (ref "FB4") (pin "1") (pinfunction "1_1") (pintype "passive"))
      (node (ref "H_VDD_LINK_CM0") (pin "1") (pinfunction "1_1") (pintype "passive"))
      (node (ref "H_VDD_LINK_CM0") (pin "2") (pinfunction "2_2") (pintype "passive"))
      (node (ref "R39") (pin "2") (pinfunction "BOT_2") (pintype "passive"))
      (node (ref "TP_VDD_LINK_CM0") (pin "1") (pinfunction "TP_1") (pintype "passive"))
    )
    (net (code "28") (name "/VDD_LINK_RS_CM1") (class "Default")
      (node (ref "FB7") (pin "1") (pinfunction "1_1") (pintype "passive"))
      (node (ref "H_VDD_LINK_CM1") (pin "1") (pinfunction "1_1") (pintype "passive"))
      (node (ref "H_VDD_LINK_CM1") (pin "2") (pinfunction "2_2") (pintype "passive"))
      (node (ref "R4") (pin "2") (pinfunction "BOT_2") (pintype "passive"))
      (node (ref "TP_VDD_LINK_CM1") (pin "1") (pinfunction "TP_1") (pintype "passive"))
    )
    (net (code "29") (name "GND") (class "Default")
      (node (ref "C1") (pin "2") (pinfunction "2_2") (pintype "passive"))
      (node (ref "C102") (pin "2") (pinfunction "2_2") (pintype "passive"))
      (node (ref "C103") (pin "2") (pinfunction "2_2") (pintype "passive"))
      (node (ref "C104") (pin "2") (pinfunction "2_2") (pintype "passive"))
      (node (ref "C105") (pin "2") (pinfunction "2_2") (pintype "passive"))
      (node (ref "C113") (pin "2") (pinfunction "2_2") (pintype "passive"))
      (node (ref "C114") (pin "2") (pinfunction "2_2") (pintype "passive"))
      (node (ref "C115") (pin "2") (pinfunction "2_2") (pintype "passive"))
      (node (ref "C116") (pin "2") (pinfunction "2_2") (pintype "passive"))
      (node (ref "C117") (pin "2") (pinfunction "2_2") (pintype "passive"))
      (node (ref "C118") (pin "2") (pinfunction "2_2") (pintype "passive"))
      (node (ref "C19") (pin "2") (pinfunction "2_2") (pintype "passive"))
      (node (ref "C2") (pin "2") (pinfunction "2_2") (pintype "passive"))
      (node (ref "C20") (pin "2") (pinfunction "2_2") (pintype "passive"))
      (node (ref "C21") (pin "2") (pinfunction "2_2") (pintype "passive"))
      (node (ref "C22") (pin "2") (pinfunction "2_2") (pintype "passive"))
      (node (ref "C23") (pin "2") (pinfunction "2_2") (pintype "passive"))
      (node (ref "C29") (pin "2") (pinfunction "2_2") (pintype "passive"))
      (node (ref "C31") (pin "2") (pinfunction "2_2") (pintype "passive"))
      (node (ref "C32") (pin "2") (pinfunction "2_2") (pintype "passive"))
      (node (ref "C33") (pin "2") (pinfunction "2_2") (pintype "passive"))
      (node (ref "C34") (pin "2") (pinfunction "2_2") (pintype "passive"))
      (node (ref "C35") (pin "2") (pinfunction "2_2") (pintype "passive"))
      (node (ref "C36") (pin "2") (pinfunction "2_2") (pintype "passive"))
      (node (ref "C37") (pin "2") (pinfunction "2_2") (pintype "passive"))
      (node (ref "C38") (pin "2") (pinfunction "2_2") (pintype "passive"))
      (node (ref "C39") (pin "2") (pinfunction "2_2") (pintype "passive"))
      (node (ref "C40") (pin "2") (pinfunction "2_2") (pintype "passive"))
      (node (ref "C43") (pin "2") (pinfunction "2_2") (pintype "passive"))
      (node (ref "C48") (pin "2") (pinfunction "2_2") (pintype "passive"))
      (node (ref "C49") (pin "2") (pinfunction "2_2") (pintype "passive"))
      (node (ref "C5") (pin "2") (pinfunction "2_2") (pintype "passive"))
      (node (ref "C50") (pin "2") (pinfunction "2_2") (pintype "passive"))
      (node (ref "C51") (pin "2") (pinfunction "2_2") (pintype "passive"))
      (node (ref "C52") (pin "2") (pinfunction "2_2") (pintype "passive"))
      (node (ref "C53") (pin "2") (pinfunction "2_2") (pintype "passive"))
      (node (ref "C6") (pin "2") (pinfunction "2_2") (pintype "passive"))
      (node (ref "C62") (pin "2") (pinfunction "2_2") (pintype "passive"))
      (node (ref "C86") (pin "2") (pinfunction "2_2") (pintype "passive"))
      (node (ref "C87") (pin "2") (pinfunction "2_2") (pintype "passive"))
      (node (ref "C88") (pin "2") (pinfunction "2_2") (pintype "passive"))
      (node (ref "C89") (pin "2") (pinfunction "2_2") (pintype "passive"))
      (node (ref "C90") (pin "2") (pinfunction "2_2") (pintype "passive"))
      (node (ref "C91") (pin "2") (pinfunction "2_2") (pintype "passive"))
      (node (ref "C92") (pin "2") (pinfunction "2_2") (pintype "passive"))
      (node (ref "C95") (pin "2") (pinfunction "2_2") (pintype "passive"))
      (node (ref "C96") (pin "2") (pinfunction "2_2") (pintype "passive"))
      (node (ref "EN_DVDD") (pin "3") (pinfunction "3_3") (pintype "passive"))
      (node (ref "EN_VDDA") (pin "3") (pinfunction "3_3") (pintype "passive"))
      (node (ref "EN_VDD_IO") (pin "3") (pinfunction "3_3") (pintype "passive"))
      (node (ref "EN_VDD_LINK_CM0") (pin "3") (pinfunction "3_3") (pintype "passive"))
      (node (ref "EN_VDD_LINK_CM1") (pin "3") (pinfunction "3_3") (pintype "passive"))
      (node (ref "H5") (pin "3") (pinfunction "3_3") (pintype "passive"))
      (node (ref "U1") (pin "12") (pinfunction "GND_12") (pintype "passive"))
      (node (ref "U1") (pin "21") (pinfunction "GND_21") (pintype "passive"))
      (node (ref "U12") (pin "12") (pinfunction "GND_12") (pintype "passive"))
      (node (ref "U12") (pin "21") (pinfunction "GND_21") (pintype "passive"))
      (node (ref "U16") (pin "12") (pinfunction "GND_12") (pintype "passive"))
      (node (ref "U16") (pin "21") (pinfunction "GND_21") (pintype "passive"))
      (node (ref "U20") (pin "6") (pinfunction "GND_6") (pintype "power_in"))
      (node (ref "U20") (pin "9") (pinfunction "GND_9") (pintype "power_in"))
      (node (ref "U21") (pin "12") (pinfunction "GND_12") (pintype "passive"))
      (node (ref "U21") (pin "21") (pinfunction "GND_21") (pintype "passive"))
      (node (ref "U3") (pin "12") (pinfunction "GND_12") (pintype "passive"))
      (node (ref "U3") (pin "21") (pinfunction "GND_21") (pintype "passive"))
    )
    (net (code "30") (name "Net-(U1-SS)") (class "Default")
      (node (ref "C62") (pin "1") (pinfunction "1_1") (pintype "passive"))
      (node (ref "U1") (pin "15") (pinfunction "SS_15") (pintype "passive"))
    )
    (net (code "31") (name "Net-(U3-SS)") (class "Default")
      (node (ref "C102") (pin "1") (pinfunction "1_1") (pintype "passive"))
      (node (ref "U3") (pin "15") (pinfunction "SS_15") (pintype "passive"))
    )
    (net (code "32") (name "Net-(U12-SS)") (class "Default")
      (node (ref "C43") (pin "1") (pinfunction "1_1") (pintype "passive"))
      (node (ref "U12") (pin "15") (pinfunction "SS_15") (pintype "passive"))
    )
    (net (code "33") (name "Net-(U16-SS)") (class "Default")
      (node (ref "C39") (pin "1") (pinfunction "1_1") (pintype "passive"))
      (node (ref "U16") (pin "15") (pinfunction "SS_15") (pintype "passive"))
    )
    (net (code "34") (name "Net-(U20-NR)") (class "Default")
      (node (ref "C91") (pin "1") (pinfunction "1_1") (pintype "passive"))
      (node (ref "U20") (pin "5") (pinfunction "NR_5") (pintype "passive"))
    )
    (net (code "35") (name "Net-(U21-SS)") (class "Default")
      (node (ref "C96") (pin "1") (pinfunction "1_1") (pintype "passive"))
      (node (ref "U21") (pin "15") (pinfunction "SS_15") (pintype "passive"))
    )
    (net (code "36") (name "VDD_BUFFER") (class "Default")
      (node (ref "C86") (pin "1") (pinfunction "1_1") (pintype "passive"))
      (node (ref "C87") (pin "1") (pinfunction "1_1") (pintype "passive"))
      (node (ref "C88") (pin "1") (pinfunction "1_1") (pintype "passive"))
      (node (ref "C89") (pin "1") (pinfunction "1_1") (pintype "passive"))
      (node (ref "FB5") (pin "2") (pinfunction "2_2") (pintype "passive"))
    )
    (net (code "37") (name "VDD_IN") (class "Default")
      (node (ref "C1") (pin "1") (pinfunction "1_1") (pintype "passive"))
      (node (ref "C105") (pin "1") (pinfunction "1_1") (pintype "passive"))
      (node (ref "C113") (pin "1") (pinfunction "1_1") (pintype "passive"))
      (node (ref "C29") (pin "1") (pinfunction "1_1") (pintype "passive"))
      (node (ref "C32") (pin "1") (pinfunction "1_1") (pintype "passive"))
      (node (ref "C90") (pin "1") (pinfunction "1_1") (pintype "passive"))
      (node (ref "H5") (pin "1") (pinfunction "1_1") (pintype "passive"))
      (node (ref "U1") (pin "5") (pinfunction "IN_5") (pintype "passive"))
      (node (ref "U1") (pin "6") (pinfunction "IN_6") (pintype "passive"))
      (node (ref "U1") (pin "7") (pinfunction "IN_7") (pintype "passive"))
      (node (ref "U1") (pin "8") (pinfunction "IN_8") (pintype "passive"))
      (node (ref "U12") (pin "5") (pinfunction "IN_5") (pintype "passive"))
      (node (ref "U12") (pin "6") (pinfunction "IN_6") (pintype "passive"))
      (node (ref "U12") (pin "7") (pinfunction "IN_7") (pintype "passive"))
      (node (ref "U12") (pin "8") (pinfunction "IN_8") (pintype "passive"))
      (node (ref "U16") (pin "5") (pinfunction "IN_5") (pintype "passive"))
      (node (ref "U16") (pin "6") (pinfunction "IN_6") (pintype "passive"))
      (node (ref "U16") (pin "7") (pinfunction "IN_7") (pintype "passive"))
      (node (ref "U16") (pin "8") (pinfunction "IN_8") (pintype "passive"))
      (node (ref "U20") (pin "1") (pinfunction "IN_1") (pintype "power_in"))
      (node (ref "U20") (pin "2") (pinfunction "IN_2") (pintype "power_in"))
      (node (ref "U21") (pin "5") (pinfunction "IN_5") (pintype "passive"))
      (node (ref "U21") (pin "6") (pinfunction "IN_6") (pintype "passive"))
      (node (ref "U21") (pin "7") (pinfunction "IN_7") (pintype "passive"))
      (node (ref "U21") (pin "8") (pinfunction "IN_8") (pintype "passive"))
      (node (ref "U3") (pin "5") (pinfunction "IN_5") (pintype "passive"))
      (node (ref "U3") (pin "6") (pinfunction "IN_6") (pintype "passive"))
      (node (ref "U3") (pin "7") (pinfunction "IN_7") (pintype "passive"))
      (node (ref "U3") (pin "8") (pinfunction "IN_8") (pintype "passive"))
    )
    (net (code "38") (name "unconnected-(U1-NC-Pad2)") (class "Default")
      (node (ref "U1") (pin "2") (pinfunction "NC_2") (pintype "passive"))
    )
    (net (code "39") (name "unconnected-(U1-NC-Pad3)") (class "Default")
      (node (ref "U1") (pin "3") (pinfunction "NC_3") (pintype "passive"))
    )
    (net (code "40") (name "unconnected-(U1-NC-Pad4)") (class "Default")
      (node (ref "U1") (pin "4") (pinfunction "NC_4") (pintype "passive"))
    )
    (net (code "41") (name "unconnected-(U1-NC-Pad13)") (class "Default")
      (node (ref "U1") (pin "13") (pinfunction "NC_13") (pintype "passive"))
    )
    (net (code "42") (name "unconnected-(U1-NC-Pad14)") (class "Default")
      (node (ref "U1") (pin "14") (pinfunction "NC_14") (pintype "passive"))
    )
    (net (code "43") (name "unconnected-(U1-NC-Pad17)") (class "Default")
      (node (ref "U1") (pin "17") (pinfunction "NC_17") (pintype "passive"))
    )
    (net (code "44") (name "unconnected-(U1-PG-Pad9)") (class "Default")
      (node (ref "U1") (pin "9") (pinfunction "PG_9") (pintype "passive"))
    )
    (net (code "45") (name "unconnected-(U3-NC-Pad2)") (class "Default")
      (node (ref "U3") (pin "2") (pinfunction "NC_2") (pintype "passive"))
    )
    (net (code "46") (name "unconnected-(U3-NC-Pad3)") (class "Default")
      (node (ref "U3") (pin "3") (pinfunction "NC_3") (pintype "passive"))
    )
    (net (code "47") (name "unconnected-(U3-NC-Pad4)") (class "Default")
      (node (ref "U3") (pin "4") (pinfunction "NC_4") (pintype "passive"))
    )
    (net (code "48") (name "unconnected-(U3-NC-Pad13)") (class "Default")
      (node (ref "U3") (pin "13") (pinfunction "NC_13") (pintype "passive"))
    )
    (net (code "49") (name "unconnected-(U3-NC-Pad14)") (class "Default")
      (node (ref "U3") (pin "14") (pinfunction "NC_14") (pintype "passive"))
    )
    (net (code "50") (name "unconnected-(U3-NC-Pad17)") (class "Default")
      (node (ref "U3") (pin "17") (pinfunction "NC_17") (pintype "passive"))
    )
    (net (code "51") (name "unconnected-(U3-PG-Pad9)") (class "Default")
      (node (ref "U3") (pin "9") (pinfunction "PG_9") (pintype "passive"))
    )
    (net (code "52") (name "unconnected-(U12-NC-Pad2)") (class "Default")
      (node (ref "U12") (pin "2") (pinfunction "NC_2") (pintype "passive"))
    )
    (net (code "53") (name "unconnected-(U12-NC-Pad3)") (class "Default")
      (node (ref "U12") (pin "3") (pinfunction "NC_3") (pintype "passive"))
    )
    (net (code "54") (name "unconnected-(U12-NC-Pad4)") (class "Default")
      (node (ref "U12") (pin "4") (pinfunction "NC_4") (pintype "passive"))
    )
    (net (code "55") (name "unconnected-(U12-NC-Pad13)") (class "Default")
      (node (ref "U12") (pin "13") (pinfunction "NC_13") (pintype "passive"))
    )
    (net (code "56") (name "unconnected-(U12-NC-Pad14)") (class "Default")
      (node (ref "U12") (pin "14") (pinfunction "NC_14") (pintype "passive"))
    )
    (net (code "57") (name "unconnected-(U12-NC-Pad17)") (class "Default")
      (node (ref "U12") (pin "17") (pinfunction "NC_17") (pintype "passive"))
    )
    (net (code "58") (name "unconnected-(U12-PG-Pad9)") (class "Default")
      (node (ref "U12") (pin "9") (pinfunction "PG_9") (pintype "passive"))
    )
    (net (code "59") (name "unconnected-(U16-NC-Pad2)") (class "Default")
      (node (ref "U16") (pin "2") (pinfunction "NC_2") (pintype "passive"))
    )
    (net (code "60") (name "unconnected-(U16-NC-Pad3)") (class "Default")
      (node (ref "U16") (pin "3") (pinfunction "NC_3") (pintype "passive"))
    )
    (net (code "61") (name "unconnected-(U16-NC-Pad4)") (class "Default")
      (node (ref "U16") (pin "4") (pinfunction "NC_4") (pintype "passive"))
    )
    (net (code "62") (name "unconnected-(U16-NC-Pad13)") (class "Default")
      (node (ref "U16") (pin "13") (pinfunction "NC_13") (pintype "passive"))
    )
    (net (code "63") (name "unconnected-(U16-NC-Pad14)") (class "Default")
      (node (ref "U16") (pin "14") (pinfunction "NC_14") (pintype "passive"))
    )
    (net (code "64") (name "unconnected-(U16-NC-Pad17)") (class "Default")
      (node (ref "U16") (pin "17") (pinfunction "NC_17") (pintype "passive"))
    )
    (net (code "65") (name "unconnected-(U16-PG-Pad9)") (class "Default")
      (node (ref "U16") (pin "9") (pinfunction "PG_9") (pintype "passive"))
    )
    (net (code "66") (name "unconnected-(U20-NC-Pad7)") (class "Default")
      (node (ref "U20") (pin "7") (pinfunction "NC_7") (pintype "passive"))
    )
    (net (code "67") (name "unconnected-(U21-NC-Pad2)") (class "Default")
      (node (ref "U21") (pin "2") (pinfunction "NC_2") (pintype "passive"))
    )
    (net (code "68") (name "unconnected-(U21-NC-Pad3)") (class "Default")
      (node (ref "U21") (pin "3") (pinfunction "NC_3") (pintype "passive"))
    )
    (net (code "69") (name "unconnected-(U21-NC-Pad4)") (class "Default")
      (node (ref "U21") (pin "4") (pinfunction "NC_4") (pintype "passive"))
    )
    (net (code "70") (name "unconnected-(U21-NC-Pad13)") (class "Default")
      (node (ref "U21") (pin "13") (pinfunction "NC_13") (pintype "passive"))
    )
    (net (code "71") (name "unconnected-(U21-NC-Pad14)") (class "Default")
      (node (ref "U21") (pin "14") (pinfunction "NC_14") (pintype "passive"))
    )
    (net (code "72") (name "unconnected-(U21-NC-Pad17)") (class "Default")
      (node (ref "U21") (pin "17") (pinfunction "NC_17") (pintype "passive"))
    )
    (net (code "73") (name "unconnected-(U21-PG-Pad9)") (class "Default")
      (node (ref "U21") (pin "9") (pinfunction "PG_9") (pintype "passive"))
    )
  )
)
